# flappy_perf.net
KiCad netlist of a schematic drawn in EAGLE
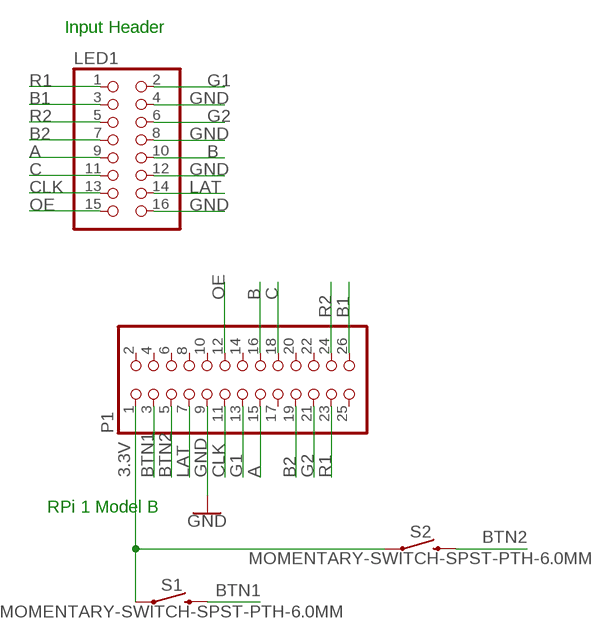
[diagram p0: schematic, sheet 1]

(export (version "E")
  (design (tool "Eeschema 10.0.6"))
  (components
    (comp (ref "LED1")
      (value "PINHD-2X8")
      (footprint "eagle-import:2X08")
      (libsource (lib "eagle-import") (part "PINHD-2X8"))
    )
    (comp (ref "P1")
      (value "PINHD-2X13")
      (footprint "eagle-import:2X13")
      (libsource (lib "eagle-import") (part "PINHD-2X13"))
    )
    (comp (ref "S1")
      (value "MOMENTARY-SWITCH-SPST-PTH-6.0MM")
      (footprint "eagle-import:TACTILE_SWITCH_PTH_6.0MM")
      (libsource (lib "eagle-import") (part "MOMENTARY-SWITCH-SPST-PTH-6.0MM"))
    )
    (comp (ref "S2")
      (value "MOMENTARY-SWITCH-SPST-PTH-6.0MM")
      (footprint "eagle-import:TACTILE_SWITCH_PTH_6.0MM")
      (libsource (lib "eagle-import") (part "MOMENTARY-SWITCH-SPST-PTH-6.0MM"))
    )
  )
  (nets
    (net (code "1") (name "/3.3V") (class "Default")
      (node (ref "P1") (pin "1") (pinfunction "1_1") (pintype "passive"))
      (node (ref "S1") (pin "1") (pinfunction "1_1") (pintype "passive"))
      (node (ref "S2") (pin "1") (pinfunction "1_1") (pintype "passive"))
    )
    (net (code "2") (name "/A") (class "Default")
      (node (ref "LED1") (pin "9") (pinfunction "9_9") (pintype "passive"))
      (node (ref "P1") (pin "15") (pinfunction "15_15") (pintype "passive"))
    )
    (net (code "3") (name "/B") (class "Default")
      (node (ref "LED1") (pin "10") (pinfunction "10_10") (pintype "passive"))
      (node (ref "P1") (pin "16") (pinfunction "16_16") (pintype "passive"))
    )
    (net (code "4") (name "/B1") (class "Default")
      (node (ref "LED1") (pin "3") (pinfunction "3_3") (pintype "passive"))
      (node (ref "P1") (pin "26") (pinfunction "26_26") (pintype "passive"))
    )
    (net (code "5") (name "/B2") (class "Default")
      (node (ref "LED1") (pin "7") (pinfunction "7_7") (pintype "passive"))
      (node (ref "P1") (pin "19") (pinfunction "19_19") (pintype "passive"))
    )
    (net (code "6") (name "/BTN1") (class "Default")
      (node (ref "P1") (pin "3") (pinfunction "3_3") (pintype "passive"))
      (node (ref "S1") (pin "3") (pinfunction "2_3") (pintype "passive"))
    )
    (net (code "7") (name "/BTN2") (class "Default")
      (node (ref "P1") (pin "5") (pinfunction "5_5") (pintype "passive"))
      (node (ref "S2") (pin "3") (pinfunction "2_3") (pintype "passive"))
    )
    (net (code "8") (name "/C") (class "Default")
      (node (ref "LED1") (pin "11") (pinfunction "11_11") (pintype "passive"))
      (node (ref "P1") (pin "18") (pinfunction "18_18") (pintype "passive"))
    )
    (net (code "9") (name "/CLK") (class "Default")
      (node (ref "LED1") (pin "13") (pinfunction "13_13") (pintype "passive"))
      (node (ref "P1") (pin "11") (pinfunction "11_11") (pintype "passive"))
    )
    (net (code "10") (name "/G1") (class "Default")
      (node (ref "LED1") (pin "2") (pinfunction "2_2") (pintype "passive"))
      (node (ref "P1") (pin "13") (pinfunction "13_13") (pintype "passive"))
    )
    (net (code "11") (name "/G2") (class "Default")
      (node (ref "LED1") (pin "6") (pinfunction "6_6") (pintype "passive"))
      (node (ref "P1") (pin "21") (pinfunction "21_21") (pintype "passive"))
    )
    (net (code "12") (name "/LAT") (class "Default")
      (node (ref "LED1") (pin "14") (pinfunction "14_14") (pintype "passive"))
      (node (ref "P1") (pin "7") (pinfunction "7_7") (pintype "passive"))
    )
    (net (code "13") (name "/OE") (class "Default")
      (node (ref "LED1") (pin "15") (pinfunction "15_15") (pintype "passive"))
      (node (ref "P1") (pin "12") (pinfunction "12_12") (pintype "passive"))
    )
    (net (code "14") (name "/R1") (class "Default")
      (node (ref "LED1") (pin "1") (pinfunction "1_1") (pintype "passive"))
      (node (ref "P1") (pin "23") (pinfunction "23_23") (pintype "passive"))
    )
    (net (code "15") (name "/R2") (class "Default")
      (node (ref "LED1") (pin "5") (pinfunction "5_5") (pintype "passive"))
      (node (ref "P1") (pin "24") (pinfunction "24_24") (pintype "passive"))
    )
    (net (code "16") (name "GND") (class "Default")
      (node (ref "LED1") (pin "12") (pinfunction "12_12") (pintype "passive"))
      (node (ref "LED1") (pin "16") (pinfunction "16_16") (pintype "passive"))
      (node (ref "LED1") (pin "4") (pinfunction "4_4") (pintype "passive"))
      (node (ref "LED1") (pin "8") (pinfunction "8_8") (pintype "passive"))
      (node (ref "P1") (pin "9") (pinfunction "9_9") (pintype "passive"))
    )
    (net (code "17") (name "unconnected-(P1-Pad2)") (class "Default")
      (node (ref "P1") (pin "2") (pinfunction "2_2") (pintype "passive"))
    )
    (net (code "18") (name "unconnected-(P1-Pad4)") (class "Default")
      (node (ref "P1") (pin "4") (pinfunction "4_4") (pintype "passive"))
    )
    (net (code "19") (name "unconnected-(P1-Pad6)") (class "Default")
      (node (ref "P1") (pin "6") (pinfunction "6_6") (pintype "passive"))
    )
    (net (code "20") (name "unconnected-(P1-Pad8)") (class "Default")
      (node (ref "P1") (pin "8") (pinfunction "8_8") (pintype "passive"))
    )
    (net (code "21") (name "unconnected-(P1-Pad10)") (class "Default")
      (node (ref "P1") (pin "10") (pinfunction "10_10") (pintype "passive"))
    )
    (net (code "22") (name "unconnected-(P1-Pad14)") (class "Default")
      (node (ref "P1") (pin "14") (pinfunction "14_14") (pintype "passive"))
    )
    (net (code "23") (name "unconnected-(P1-Pad17)") (class "Default")
      (node (ref "P1") (pin "17") (pinfunction "17_17") (pintype "passive"))
    )
    (net (code "24") (name "unconnected-(P1-Pad20)") (class "Default")
      (node (ref "P1") (pin "20") (pinfunction "20_20") (pintype "passive"))
    )
    (net (code "25") (name "unconnected-(P1-Pad22)") (class "Default")
      (node (ref "P1") (pin "22") (pinfunction "22_22") (pintype "passive"))
    )
    (net (code "26") (name "unconnected-(P1-Pad25)") (class "Default")
      (node (ref "P1") (pin "25") (pinfunction "25_25") (pintype "passive"))
    )
  )
)
